# breeze_wireless.net
KiCad netlist of a schematic drawn in Altium Designer
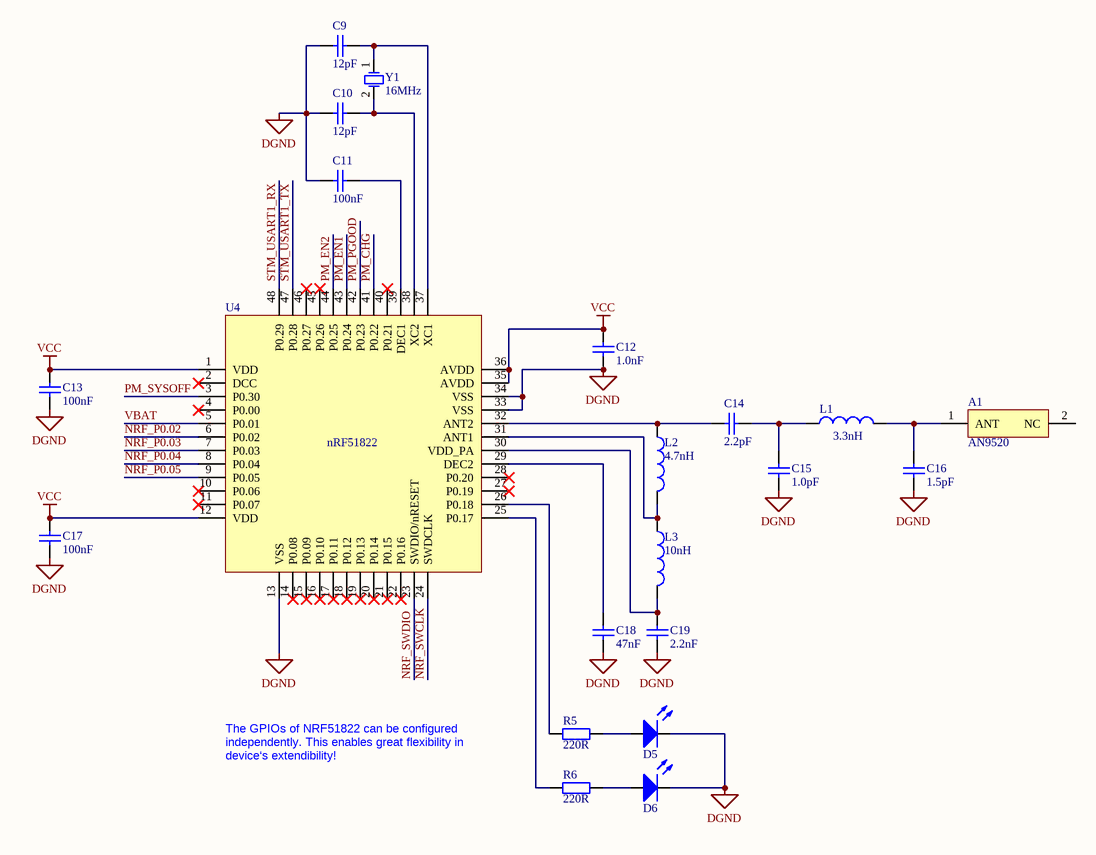
[diagram p0: breeze_wireless.SchDoc]

(export (version "E")
  (design (tool "Eeschema 10.0.6"))
  (components
    (comp (ref "A1")
      (value "AN9520")
      (footprint "AN9520")
      (description "2.4GHz Wireless Communication Antenna")
      (libsource (lib "breeze_design_library") (part "AN9520"))
    )
    (comp (ref "C9")
      (value "12pF")
      (footprint "SMD-0603")
      (description "Capacitor")
      (fields (field (name "Comment") "CAP-0603"))
      (libsource (lib "breeze_design_library") (part "CAP-0603"))
    )
    (comp (ref "C10")
      (value "12pF")
      (footprint "SMD-0603")
      (description "Capacitor")
      (fields (field (name "Comment") "CAP-0603"))
      (libsource (lib "breeze_design_library") (part "CAP-0603"))
    )
    (comp (ref "C11")
      (value "100nF")
      (footprint "SMD-0603")
      (description "Capacitor")
      (fields (field (name "Comment") "CAP-0603"))
      (libsource (lib "breeze_design_library") (part "CAP-0603"))
    )
    (comp (ref "C12")
      (value "1.0nF")
      (footprint "SMD-0603")
      (description "Capacitor")
      (fields (field (name "Comment") "CAP-0603"))
      (libsource (lib "breeze_design_library") (part "CAP-0603"))
    )
    (comp (ref "C13")
      (value "100nF")
      (footprint "SMD-0603")
      (description "Capacitor")
      (fields (field (name "Comment") "CAP-0603"))
      (libsource (lib "breeze_design_library") (part "CAP-0603"))
    )
    (comp (ref "C14")
      (value "2.2pF")
      (footprint "SMD-0603")
      (description "Capacitor")
      (fields (field (name "Comment") "CAP-0603"))
      (libsource (lib "breeze_design_library") (part "CAP-0603"))
    )
    (comp (ref "C15")
      (value "1.0pF")
      (footprint "SMD-0603")
      (description "Capacitor")
      (fields (field (name "Comment") "CAP-0603"))
      (libsource (lib "breeze_design_library") (part "CAP-0603"))
    )
    (comp (ref "C16")
      (value "1.5pF")
      (footprint "SMD-0603")
      (description "Capacitor")
      (fields (field (name "Comment") "CAP-0603"))
      (libsource (lib "breeze_design_library") (part "CAP-0603"))
    )
    (comp (ref "C17")
      (value "100nF")
      (footprint "SMD-0603")
      (description "Capacitor")
      (fields (field (name "Comment") "CAP-0603"))
      (libsource (lib "breeze_design_library") (part "CAP-0603"))
    )
    (comp (ref "C18")
      (value "47nF")
      (footprint "SMD-0603")
      (description "Capacitor")
      (fields (field (name "Comment") "CAP-0603"))
      (libsource (lib "breeze_design_library") (part "CAP-0603"))
    )
    (comp (ref "C19")
      (value "2.2nF")
      (footprint "SMD-0603")
      (description "Capacitor")
      (fields (field (name "Comment") "CAP-0603"))
      (libsource (lib "breeze_design_library") (part "CAP-0603"))
    )
    (comp (ref "D5")
      (value "LED-0603")
      (footprint "SMD-0603")
      (description "LED")
      (libsource (lib "breeze_design_library") (part "LED-0603"))
    )
    (comp (ref "D6")
      (value "LED-0603")
      (footprint "SMD-0603")
      (description "LED")
      (libsource (lib "breeze_design_library") (part "LED-0603"))
    )
    (comp (ref "L1")
      (value "3.3nH")
      (footprint "SMD-0402")
      (description "Inductor")
      (fields (field (name "Comment") "IND-0402"))
      (libsource (lib "breeze_design_library") (part "IND-0402"))
    )
    (comp (ref "L2")
      (value "4.7nH")
      (footprint "SMD-0402")
      (description "Inductor")
      (fields (field (name "Comment") "IND-0402"))
      (libsource (lib "breeze_design_library") (part "IND-0402"))
    )
    (comp (ref "L3")
      (value "10nH")
      (footprint "SMD-0402")
      (description "Inductor")
      (fields (field (name "Comment") "IND-0402"))
      (libsource (lib "breeze_design_library") (part "IND-0402"))
    )
    (comp (ref "R5")
      (value "220R")
      (footprint "SMD-0603")
      (description "Resistor")
      (fields (field (name "Comment") "RES-0603"))
      (libsource (lib "breeze_design_library") (part "RES-0603"))
    )
    (comp (ref "R6")
      (value "220R")
      (footprint "SMD-0603")
      (description "Resistor")
      (fields (field (name "Comment") "RES-0603"))
      (libsource (lib "breeze_design_library") (part "RES-0603"))
    )
    (comp (ref "U4")
      (value "nRF51822")
      (footprint "QFN-48")
      (description "Multiprotocol Bluetooth 4.0 low energy/2.4 GHz RF SoC")
      (libsource (lib "breeze_design_library") (part "nRF51822"))
    )
    (comp (ref "Y1")
      (value "16MHz")
      (footprint "SMD-5032")
      (description "Passive Crystal Oscillator")
      (fields (field (name "Comment") "XTAL-5032"))
      (libsource (lib "breeze_design_library") (part "XTAL-5032"))
    )
  )
  (nets
    (net (code "1") (name "/NRF_P0.02") (class "Default")
      (node (ref "U4") (pin "6") (pinfunction "P0.02_6") (pintype "passive"))
    )
    (net (code "2") (name "/NRF_P0.03") (class "Default")
      (node (ref "U4") (pin "7") (pinfunction "P0.03_7") (pintype "passive"))
    )
    (net (code "3") (name "/NRF_P0.04") (class "Default")
      (node (ref "U4") (pin "8") (pinfunction "P0.04_8") (pintype "passive"))
    )
    (net (code "4") (name "/NRF_P0.05") (class "Default")
      (node (ref "U4") (pin "9") (pinfunction "P0.05_9") (pintype "passive"))
    )
    (net (code "5") (name "/NRF_SWCLK") (class "Default")
      (node (ref "U4") (pin "24") (pinfunction "SWDCLK_24") (pintype "passive"))
    )
    (net (code "6") (name "/NRF_SWDIO") (class "Default")
      (node (ref "U4") (pin "23") (pinfunction "SWDIO/nRESET_23") (pintype "passive"))
    )
    (net (code "7") (name "/PM_CHG") (class "Default")
      (node (ref "U4") (pin "41") (pinfunction "P0.22_41") (pintype "passive"))
    )
    (net (code "8") (name "/PM_EN1") (class "Default")
      (node (ref "U4") (pin "43") (pinfunction "P0.24_43") (pintype "passive"))
    )
    (net (code "9") (name "/PM_EN2") (class "Default")
      (node (ref "U4") (pin "44") (pinfunction "P0.25_44") (pintype "passive"))
    )
    (net (code "10") (name "/PM_PGOOD") (class "Default")
      (node (ref "U4") (pin "42") (pinfunction "P0.23_42") (pintype "passive"))
    )
    (net (code "11") (name "/PM_SYSOFF") (class "Default")
      (node (ref "U4") (pin "3") (pinfunction "P0.30_3") (pintype "passive"))
    )
    (net (code "12") (name "/STM_USART1_RX") (class "Default")
      (node (ref "U4") (pin "48") (pinfunction "P0.29_48") (pintype "passive"))
    )
    (net (code "13") (name "/STM_USART1_TX") (class "Default")
      (node (ref "U4") (pin "47") (pinfunction "P0.28_47") (pintype "passive"))
    )
    (net (code "14") (name "/VBAT") (class "Default")
      (node (ref "U4") (pin "5") (pinfunction "P0.01_5") (pintype "passive"))
    )
    (net (code "15") (name "DGND") (class "Default")
      (node (ref "C10") (pin "2") (pinfunction "2_2") (pintype "passive"))
      (node (ref "C11") (pin "2") (pinfunction "2_2") (pintype "passive"))
      (node (ref "C12") (pin "2") (pinfunction "2_2") (pintype "passive"))
      (node (ref "C13") (pin "2") (pinfunction "2_2") (pintype "passive"))
      (node (ref "C15") (pin "2") (pinfunction "2_2") (pintype "passive"))
      (node (ref "C16") (pin "2") (pinfunction "2_2") (pintype "passive"))
      (node (ref "C17") (pin "2") (pinfunction "2_2") (pintype "passive"))
      (node (ref "C18") (pin "2") (pinfunction "2_2") (pintype "passive"))
      (node (ref "C19") (pin "2") (pinfunction "2_2") (pintype "passive"))
      (node (ref "C9") (pin "2") (pinfunction "2_2") (pintype "passive"))
      (node (ref "D5") (pin "2") (pinfunction "K_2") (pintype "passive"))
      (node (ref "D6") (pin "2") (pinfunction "K_2") (pintype "passive"))
      (node (ref "U4") (pin "13") (pinfunction "VSS_13") (pintype "passive"))
      (node (ref "U4") (pin "33") (pinfunction "VSS_33") (pintype "passive"))
      (node (ref "U4") (pin "34") (pinfunction "VSS_34") (pintype "passive"))
    )
    (net (code "16") (name "Net-(A1-ANT)") (class "Default")
      (node (ref "A1") (pin "1") (pinfunction "ANT_1") (pintype "passive"))
      (node (ref "C16") (pin "1") (pinfunction "1_1") (pintype "passive"))
      (node (ref "L1") (pin "2") (pinfunction "2_2") (pintype "passive"))
    )
    (net (code "17") (name "Net-(C14-Pad2)") (class "Default")
      (node (ref "C14") (pin "2") (pinfunction "2_2") (pintype "passive"))
      (node (ref "C15") (pin "1") (pinfunction "1_1") (pintype "passive"))
      (node (ref "L1") (pin "1") (pinfunction "1_1") (pintype "passive"))
    )
    (net (code "18") (name "Net-(D5-A)") (class "Default")
      (node (ref "D5") (pin "1") (pinfunction "A_1") (pintype "passive"))
      (node (ref "R5") (pin "2") (pinfunction "2_2") (pintype "passive"))
    )
    (net (code "19") (name "Net-(D6-A)") (class "Default")
      (node (ref "D6") (pin "1") (pinfunction "A_1") (pintype "passive"))
      (node (ref "R6") (pin "2") (pinfunction "2_2") (pintype "passive"))
    )
    (net (code "20") (name "Net-(U4-ANT1)") (class "Default")
      (node (ref "L2") (pin "2") (pinfunction "2_2") (pintype "passive"))
      (node (ref "L3") (pin "1") (pinfunction "1_1") (pintype "passive"))
      (node (ref "U4") (pin "31") (pinfunction "ANT1_31") (pintype "passive"))
    )
    (net (code "21") (name "Net-(U4-ANT2)") (class "Default")
      (node (ref "C14") (pin "1") (pinfunction "1_1") (pintype "passive"))
      (node (ref "L2") (pin "1") (pinfunction "1_1") (pintype "passive"))
      (node (ref "U4") (pin "32") (pinfunction "ANT2_32") (pintype "passive"))
    )
    (net (code "22") (name "Net-(U4-DEC1)") (class "Default")
      (node (ref "C11") (pin "1") (pinfunction "1_1") (pintype "passive"))
      (node (ref "U4") (pin "39") (pinfunction "DEC1_39") (pintype "passive"))
    )
    (net (code "23") (name "Net-(U4-DEC2)") (class "Default")
      (node (ref "C18") (pin "1") (pinfunction "1_1") (pintype "passive"))
      (node (ref "U4") (pin "29") (pinfunction "DEC2_29") (pintype "passive"))
    )
    (net (code "24") (name "Net-(U4-P0.17)") (class "Default")
      (node (ref "R6") (pin "1") (pinfunction "1_1") (pintype "passive"))
      (node (ref "U4") (pin "25") (pinfunction "P0.17_25") (pintype "passive"))
    )
    (net (code "25") (name "Net-(U4-P0.18)") (class "Default")
      (node (ref "R5") (pin "1") (pinfunction "1_1") (pintype "passive"))
      (node (ref "U4") (pin "26") (pinfunction "P0.18_26") (pintype "passive"))
    )
    (net (code "26") (name "Net-(U4-VDD_PA)") (class "Default")
      (node (ref "C19") (pin "1") (pinfunction "1_1") (pintype "passive"))
      (node (ref "L3") (pin "2") (pinfunction "2_2") (pintype "passive"))
      (node (ref "U4") (pin "30") (pinfunction "VDD_PA_30") (pintype "passive"))
    )
    (net (code "27") (name "Net-(U4-XC1)") (class "Default")
      (node (ref "C9") (pin "1") (pinfunction "1_1") (pintype "passive"))
      (node (ref "U4") (pin "37") (pinfunction "XC1_37") (pintype "passive"))
      (node (ref "Y1") (pin "1") (pinfunction "OSC1_1") (pintype "passive"))
    )
    (net (code "28") (name "Net-(U4-XC2)") (class "Default")
      (node (ref "C10") (pin "1") (pinfunction "1_1") (pintype "passive"))
      (node (ref "U4") (pin "38") (pinfunction "XC2_38") (pintype "passive"))
      (node (ref "Y1") (pin "2") (pinfunction "OSC2_2") (pintype "passive"))
    )
    (net (code "29") (name "VCC") (class "Default")
      (node (ref "C12") (pin "1") (pinfunction "1_1") (pintype "passive"))
      (node (ref "C13") (pin "1") (pinfunction "1_1") (pintype "passive"))
      (node (ref "C17") (pin "1") (pinfunction "1_1") (pintype "passive"))
      (node (ref "U4") (pin "1") (pinfunction "VDD_1") (pintype "passive"))
      (node (ref "U4") (pin "12") (pinfunction "VDD_12") (pintype "passive"))
      (node (ref "U4") (pin "35") (pinfunction "AVDD_35") (pintype "passive"))
      (node (ref "U4") (pin "36") (pinfunction "AVDD_36") (pintype "passive"))
    )
    (net (code "30") (name "unconnected-(A1-NC-Pad2)") (class "Default")
      (node (ref "A1") (pin "2") (pinfunction "NC_2") (pintype "passive"))
    )
    (net (code "31") (name "unconnected-(U4-DCC-Pad2)") (class "Default")
      (node (ref "U4") (pin "2") (pinfunction "DCC_2") (pintype "passive+no_connect"))
    )
    (net (code "32") (name "unconnected-(U4-P0.00-Pad4)") (class "Default")
      (node (ref "U4") (pin "4") (pinfunction "P0.00_4") (pintype "passive+no_connect"))
    )
    (net (code "33") (name "unconnected-(U4-P0.06-Pad10)") (class "Default")
      (node (ref "U4") (pin "10") (pinfunction "P0.06_10") (pintype "passive+no_connect"))
    )
    (net (code "34") (name "unconnected-(U4-P0.07-Pad11)") (class "Default")
      (node (ref "U4") (pin "11") (pinfunction "P0.07_11") (pintype "passive+no_connect"))
    )
    (net (code "35") (name "unconnected-(U4-P0.08-Pad14)") (class "Default")
      (node (ref "U4") (pin "14") (pinfunction "P0.08_14") (pintype "passive+no_connect"))
    )
    (net (code "36") (name "unconnected-(U4-P0.09-Pad15)") (class "Default")
      (node (ref "U4") (pin "15") (pinfunction "P0.09_15") (pintype "passive+no_connect"))
    )
    (net (code "37") (name "unconnected-(U4-P0.10-Pad16)") (class "Default")
      (node (ref "U4") (pin "16") (pinfunction "P0.10_16") (pintype "passive+no_connect"))
    )
    (net (code "38") (name "unconnected-(U4-P0.11-Pad17)") (class "Default")
      (node (ref "U4") (pin "17") (pinfunction "P0.11_17") (pintype "passive+no_connect"))
    )
    (net (code "39") (name "unconnected-(U4-P0.12-Pad18)") (class "Default")
      (node (ref "U4") (pin "18") (pinfunction "P0.12_18") (pintype "passive+no_connect"))
    )
    (net (code "40") (name "unconnected-(U4-P0.13-Pad19)") (class "Default")
      (node (ref "U4") (pin "19") (pinfunction "P0.13_19") (pintype "passive+no_connect"))
    )
    (net (code "41") (name "unconnected-(U4-P0.14-Pad20)") (class "Default")
      (node (ref "U4") (pin "20") (pinfunction "P0.14_20") (pintype "passive+no_connect"))
    )
    (net (code "42") (name "unconnected-(U4-P0.15-Pad21)") (class "Default")
      (node (ref "U4") (pin "21") (pinfunction "P0.15_21") (pintype "passive+no_connect"))
    )
    (net (code "43") (name "unconnected-(U4-P0.16-Pad22)") (class "Default")
      (node (ref "U4") (pin "22") (pinfunction "P0.16_22") (pintype "passive+no_connect"))
    )
    (net (code "44") (name "unconnected-(U4-P0.19-Pad27)") (class "Default")
      (node (ref "U4") (pin "27") (pinfunction "P0.19_27") (pintype "passive+no_connect"))
    )
    (net (code "45") (name "unconnected-(U4-P0.20-Pad28)") (class "Default")
      (node (ref "U4") (pin "28") (pinfunction "P0.20_28") (pintype "passive+no_connect"))
    )
    (net (code "46") (name "unconnected-(U4-P0.21-Pad40)") (class "Default")
      (node (ref "U4") (pin "40") (pinfunction "P0.21_40") (pintype "passive+no_connect"))
    )
    (net (code "47") (name "unconnected-(U4-P0.26-Pad45)") (class "Default")
      (node (ref "U4") (pin "45") (pinfunction "P0.26_45") (pintype "passive+no_connect"))
    )
    (net (code "48") (name "unconnected-(U4-P0.27-Pad46)") (class "Default")
      (node (ref "U4") (pin "46") (pinfunction "P0.27_46") (pintype "passive+no_connect"))
    )
  )
)
